# TSOC_PSoC4L.net
KiCad netlist of a schematic drawn in EAGLE
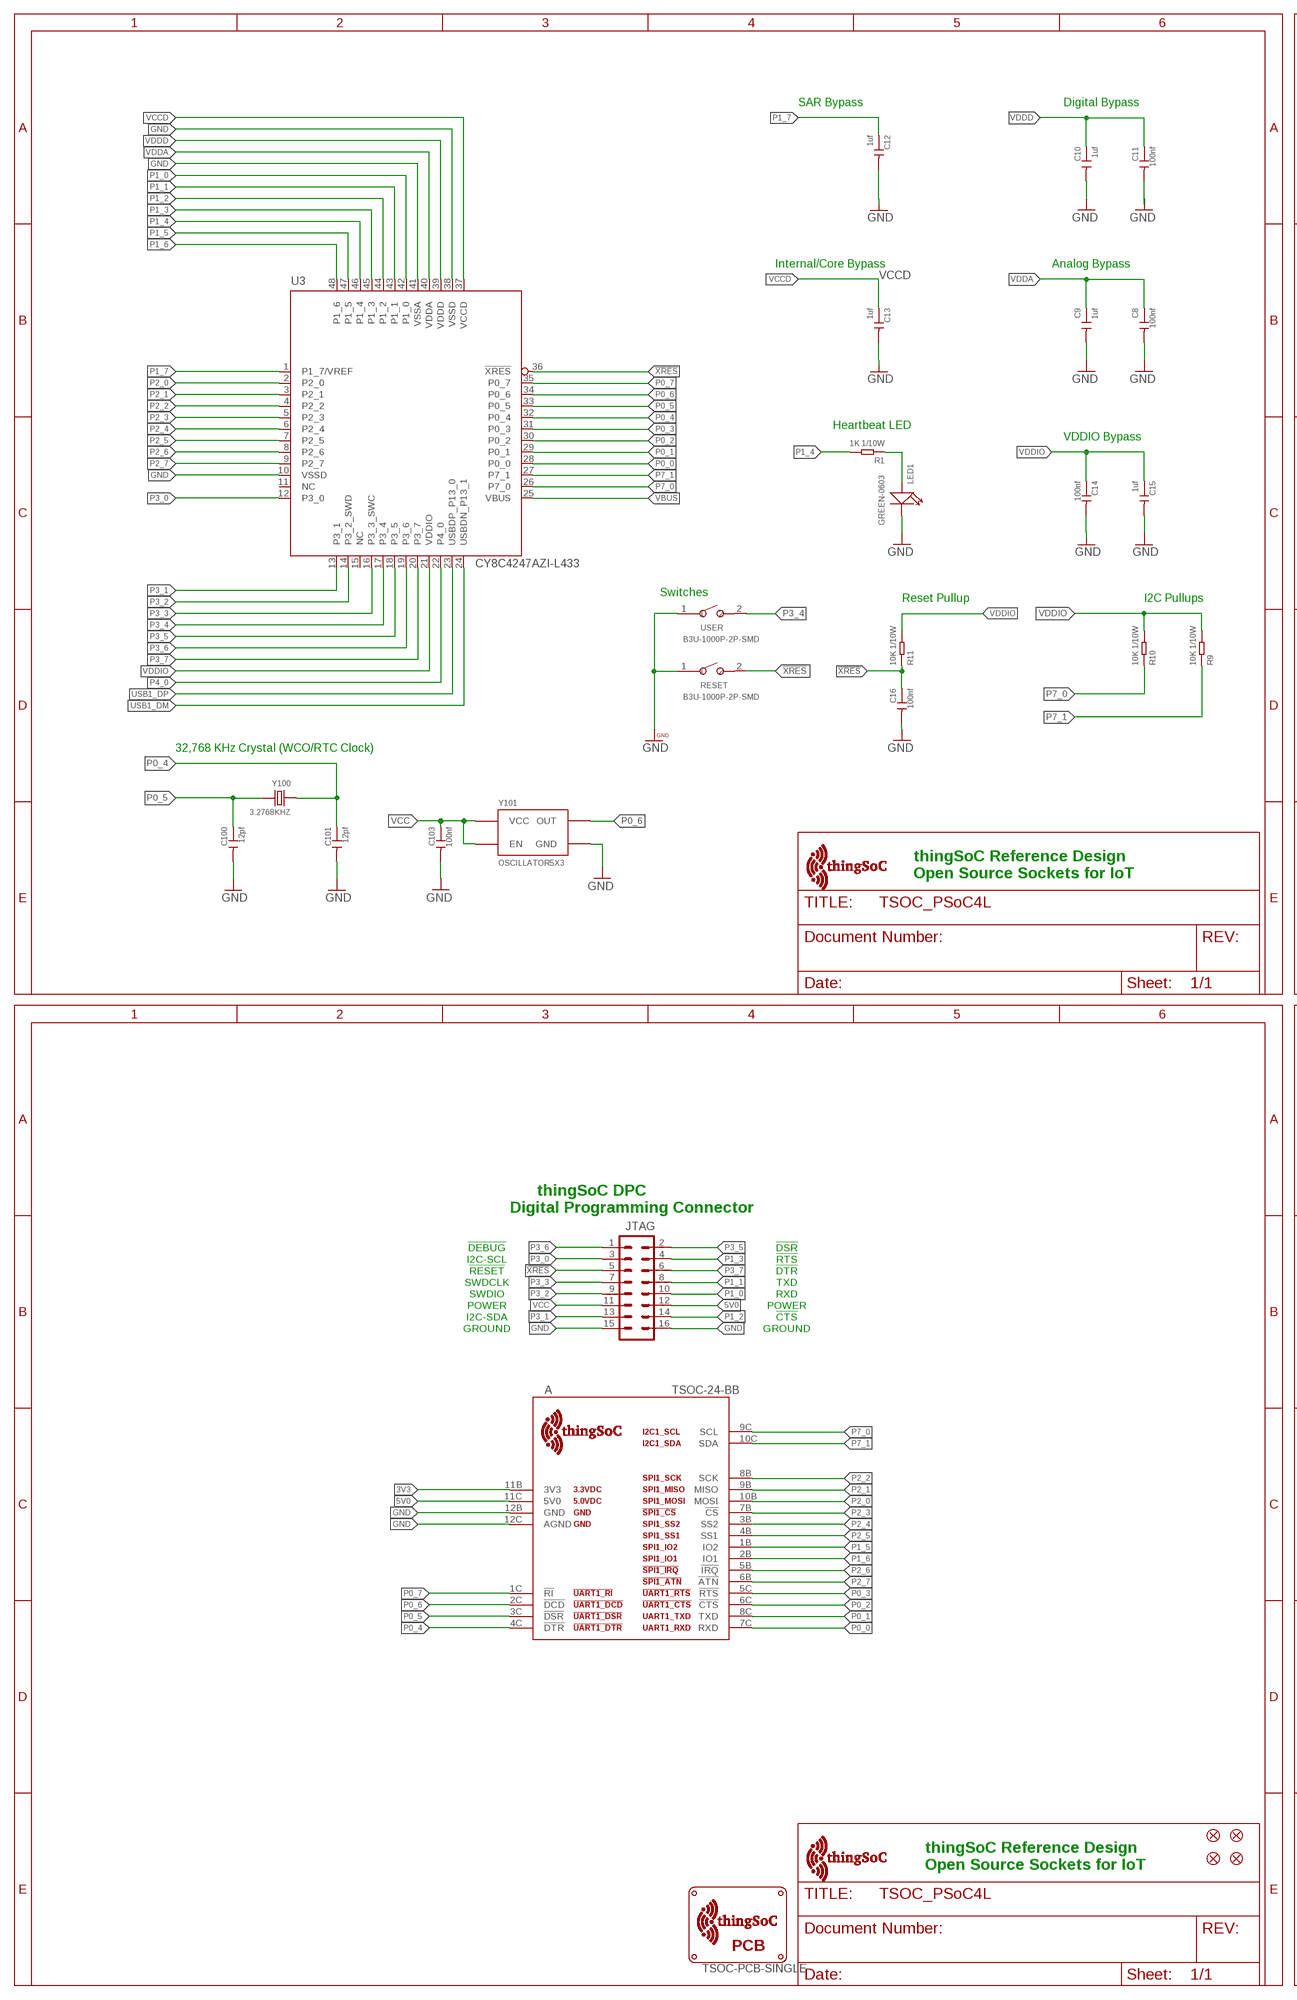
[diagram p0: schematic, sheet 1, part 1 of 2]
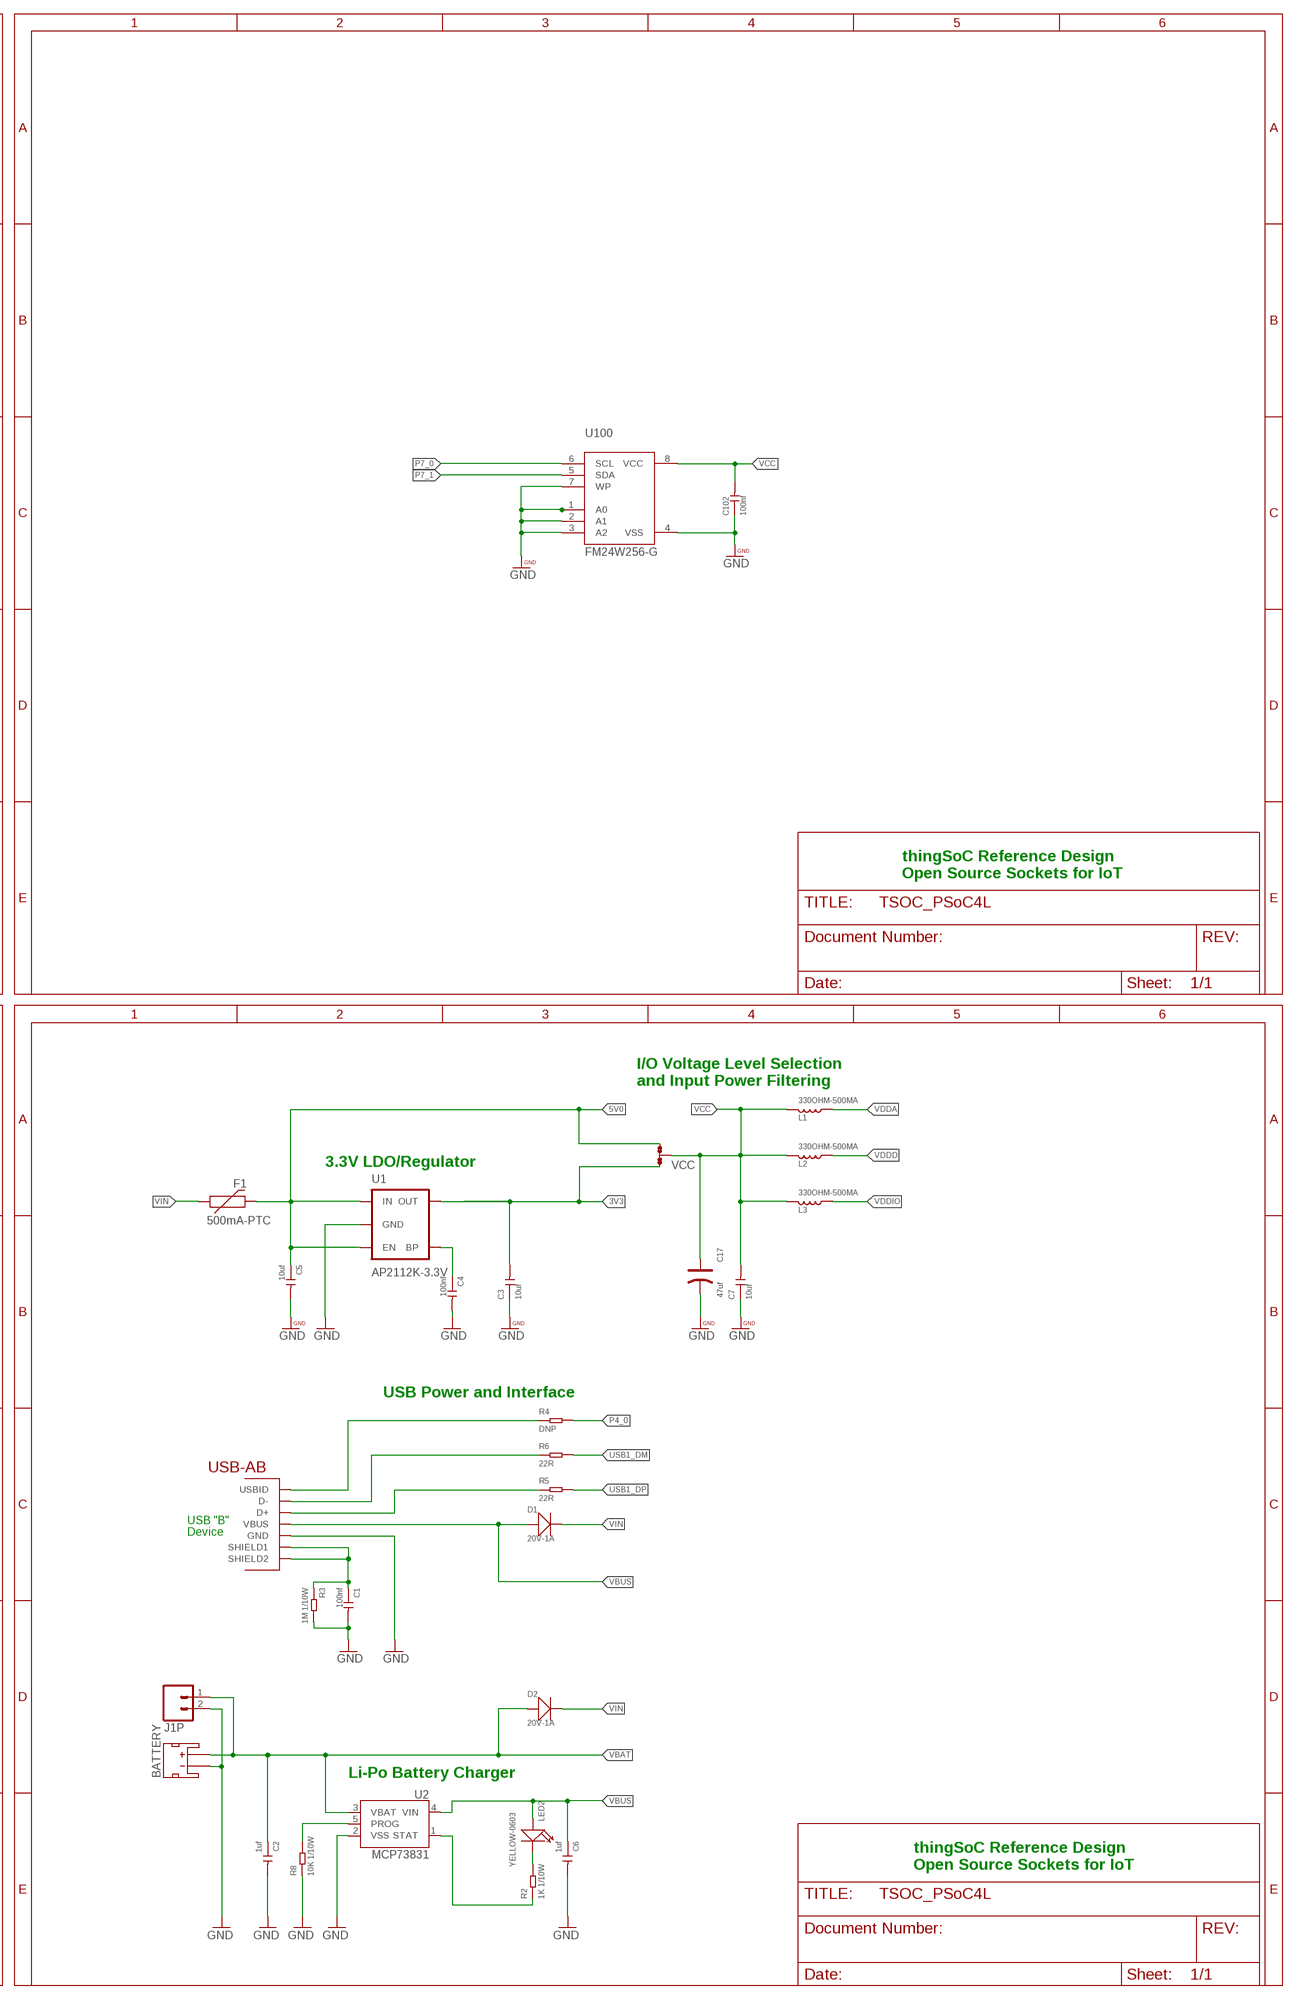
[diagram p1: schematic, sheet 1, part 2 of 2]

(export (version "E")
  (design (tool "Eeschema 10.0.6"))
  (components
    (comp (ref "A")
      (value "TSOC-24-BB")
      (footprint "eagle-import:TSOC-BB-S24")
      (libsource (lib "eagle-import") (part "TSOC-24-BB"))
    )
    (comp (ref "BATTERY")
      (value "JST_2MM_MALE")
      (footprint "eagle-import:JST-2-SMD")
      (libsource (lib "eagle-import") (part "JST_2MM_MALE"))
    )
    (comp (ref "C1")
      (value "100nf")
      (footprint "eagle-import:C0603")
      (fields (field (name "MPN") "CC0603KRX7R9BB104"))
      (libsource (lib "eagle-import") (part "CERAMIC-100NF-50V-10%-X7R(0603)"))
    )
    (comp (ref "C2")
      (value "1uf")
      (footprint "eagle-import:C0603")
      (fields (field (name "MPN") "CC0603KRX7R8BB105"))
      (libsource (lib "eagle-import") (part "CERAMIC-1UF-25V-10%-X7R(0603)"))
    )
    (comp (ref "C3")
      (value "10uf")
      (footprint "eagle-import:C0603")
      (fields (field (name "MPN") "CC0603KRX5R6BB106"))
      (libsource (lib "eagle-import") (part "CERAMIC-10UF-10V-10%-X5R(0603)"))
    )
    (comp (ref "C4")
      (value "100nf")
      (footprint "eagle-import:C0603")
      (fields (field (name "MPN") "CC0603KRX7R9BB104"))
      (libsource (lib "eagle-import") (part "CERAMIC-100NF-50V-10%-X7R(0603)"))
    )
    (comp (ref "C5")
      (value "10uf")
      (footprint "eagle-import:C0603")
      (fields (field (name "MPN") "CC0603KRX5R6BB106"))
      (libsource (lib "eagle-import") (part "CERAMIC-10UF-10V-10%-X5R(0603)"))
    )
    (comp (ref "C6")
      (value "1uf")
      (footprint "eagle-import:C0603")
      (fields (field (name "MPN") "CC0603KRX7R8BB105"))
      (libsource (lib "eagle-import") (part "CERAMIC-1UF-25V-10%-X7R(0603)"))
    )
    (comp (ref "C7")
      (value "10uf")
      (footprint "eagle-import:C0603")
      (fields (field (name "MPN") "CC0603KRX5R6BB106"))
      (libsource (lib "eagle-import") (part "CERAMIC-10UF-10V-10%-X5R(0603)"))
    )
    (comp (ref "C8")
      (value "100nf")
      (footprint "eagle-import:C0603")
      (fields (field (name "MPN") "CC0603KRX7R9BB104"))
      (libsource (lib "eagle-import") (part "CERAMIC-100NF-50V-10%-X7R(0603)"))
    )
    (comp (ref "C9")
      (value "1uf")
      (footprint "eagle-import:C0603")
      (fields (field (name "MPN") "CC0603KRX7R8BB105"))
      (libsource (lib "eagle-import") (part "CERAMIC-1UF-25V-10%-X7R(0603)"))
    )
    (comp (ref "C10")
      (value "1uf")
      (footprint "eagle-import:C0603")
      (fields (field (name "MPN") "CC0603KRX7R8BB105"))
      (libsource (lib "eagle-import") (part "CERAMIC-1UF-25V-10%-X7R(0603)"))
    )
    (comp (ref "C11")
      (value "100nf")
      (footprint "eagle-import:C0603")
      (fields (field (name "MPN") "CC0603KRX7R9BB104"))
      (libsource (lib "eagle-import") (part "CERAMIC-100NF-50V-10%-X7R(0603)"))
    )
    (comp (ref "C12")
      (value "1uf")
      (footprint "eagle-import:C0603")
      (fields (field (name "MPN") "CC0603KRX7R8BB105"))
      (libsource (lib "eagle-import") (part "CERAMIC-1UF-25V-10%-X7R(0603)"))
    )
    (comp (ref "C13")
      (value "1uf")
      (footprint "eagle-import:C0603")
      (fields (field (name "MPN") "CC0603KRX7R8BB105"))
      (libsource (lib "eagle-import") (part "CERAMIC-1UF-25V-10%-X7R(0603)"))
    )
    (comp (ref "C14")
      (value "100nf")
      (footprint "eagle-import:C0603")
      (fields (field (name "MPN") "CC0603KRX7R9BB104"))
      (libsource (lib "eagle-import") (part "CERAMIC-100NF-50V-10%-X7R(0603)"))
    )
    (comp (ref "C15")
      (value "1uf")
      (footprint "eagle-import:C0603")
      (fields (field (name "MPN") "CC0603KRX7R8BB105"))
      (libsource (lib "eagle-import") (part "CERAMIC-1UF-25V-10%-X7R(0603)"))
    )
    (comp (ref "C16")
      (value "100nf")
      (footprint "eagle-import:C0603")
      (fields (field (name "MPN") "CC0603KRX7R9BB104"))
      (libsource (lib "eagle-import") (part "CERAMIC-100NF-50V-10%-X7R(0603)"))
    )
    (comp (ref "C17")
      (value "47uf")
      (footprint "eagle-import:AVX-A")
      (fields (field (name "MPN") "TAJA476*006#NJ"))
      (libsource (lib "eagle-import") (part "TANTALUM-SMD-47UF-6.3V(AVX-A)"))
    )
    (comp (ref "C100")
      (value "12pf")
      (footprint "eagle-import:C0603")
      (fields (field (name "MPN") "CC0603JRNPO9BN120"))
      (libsource (lib "eagle-import") (part "CERAMIC-12PF-50V-5%-NPO(0603)"))
    )
    (comp (ref "C101")
      (value "12pf")
      (footprint "eagle-import:C0603")
      (fields (field (name "MPN") "CC0603JRNPO9BN120"))
      (libsource (lib "eagle-import") (part "CERAMIC-12PF-50V-5%-NPO(0603)"))
    )
    (comp (ref "C102")
      (value "100nf")
      (footprint "eagle-import:C0603")
      (fields (field (name "MPN") "CC0603KRX7R9BB104"))
      (libsource (lib "eagle-import") (part "CERAMIC-100NF-50V-10%-X7R(0603)"))
    )
    (comp (ref "C103")
      (value "100nf")
      (footprint "eagle-import:C0603")
      (fields (field (name "MPN") "CC0603KRX7R9BB104"))
      (libsource (lib "eagle-import") (part "CERAMIC-100NF-50V-10%-X7R(0603)"))
    )
    (comp (ref "D1")
      (value "20V-1A")
      (footprint "eagle-import:SOD-123")
      (fields (field (name "MPN") "B5819W"))
      (libsource (lib "eagle-import") (part "SMD-DIODE-SCHOTTKY-20V-1A(SOD-123)"))
    )
    (comp (ref "D2")
      (value "20V-1A")
      (footprint "eagle-import:SOD-123")
      (fields (field (name "MPN") "B5819W"))
      (libsource (lib "eagle-import") (part "SMD-DIODE-SCHOTTKY-20V-1A(SOD-123)"))
    )
    (comp (ref "F1")
      (value "500mA-PTC")
      (footprint "eagle-import:PTC-1206")
      (libsource (lib "eagle-import") (part "PTCSMD"))
    )
    (comp (ref "FID1")
      (value "FIDUCIALUFIDUCIAL")
      (footprint "eagle-import:MICRO-FIDUCIAL")
      (libsource (lib "eagle-import") (part "FIDUCIALUFIDUCIAL"))
    )
    (comp (ref "FID2")
      (value "FIDUCIALUFIDUCIAL")
      (footprint "eagle-import:MICRO-FIDUCIAL")
      (libsource (lib "eagle-import") (part "FIDUCIALUFIDUCIAL"))
    )
    (comp (ref "FID3")
      (value "FIDUCIALUFIDUCIAL")
      (footprint "eagle-import:MICRO-FIDUCIAL")
      (libsource (lib "eagle-import") (part "FIDUCIALUFIDUCIAL"))
    )
    (comp (ref "FID4")
      (value "FIDUCIALUFIDUCIAL")
      (footprint "eagle-import:MICRO-FIDUCIAL")
      (libsource (lib "eagle-import") (part "FIDUCIALUFIDUCIAL"))
    )
    (comp (ref "J1P")
      (value "M02-JST-2-PTH-NO_SILK")
      (footprint "eagle-import:JST-2-PTH-NS")
      (libsource (lib "eagle-import") (part "M02-JST-2-PTH-NO_SILK"))
    )
    (comp (ref "JTAG")
      (value "M08X2")
      (footprint "eagle-import:2X8")
      (libsource (lib "eagle-import") (part "M08X2"))
    )
    (comp (ref "L1")
      (value "330OHM-500MA")
      (footprint "eagle-import:L0603")
      (fields (field (name "MPN") "BLM18AG121SN1D"))
      (libsource (lib "eagle-import") (part "SMD-FERRITE-CHIP-120-OHM-500MA(0603)"))
    )
    (comp (ref "L2")
      (value "330OHM-500MA")
      (footprint "eagle-import:L0603")
      (fields (field (name "MPN") "BLM18AG121SN1D"))
      (libsource (lib "eagle-import") (part "SMD-FERRITE-CHIP-120-OHM-500MA(0603)"))
    )
    (comp (ref "L3")
      (value "330OHM-500MA")
      (footprint "eagle-import:L0603")
      (fields (field (name "MPN") "BLM18AG121SN1D"))
      (libsource (lib "eagle-import") (part "SMD-FERRITE-CHIP-120-OHM-500MA(0603)"))
    )
    (comp (ref "LED1")
      (value "GREEN-0603")
      (footprint "eagle-import:LED-0603")
      (fields (field (name "MPN") "19-217-G7C-AN1P2-3T"))
      (libsource (lib "eagle-import") (part "SMD-LED-CLEAR-GREEN(0603)"))
    )
    (comp (ref "LED2")
      (value "YELLOW-0603")
      (footprint "eagle-import:LED-0603")
      (fields (field (name "MPN") "19-217-Y5C-AM1N1VY-3T"))
      (libsource (lib "eagle-import") (part "SMD-LED-CLEAR-YELLOW(0603)"))
    )
    (comp (ref "R1")
      (value "1K 1/10W")
      (footprint "eagle-import:R0603")
      (fields (field (name "MPN") "RC0603JR-071KL"))
      (libsource (lib "eagle-import") (part "SMD-RES-1K-5%-1/10W(0603)"))
    )
    (comp (ref "R2")
      (value "1K 1/10W")
      (footprint "eagle-import:R0603")
      (fields (field (name "MPN") "RC0603JR-071KL"))
      (libsource (lib "eagle-import") (part "SMD-RES-1K-5%-1/10W(0603)"))
    )
    (comp (ref "R3")
      (value "1M 1/10W")
      (footprint "eagle-import:R0603")
      (fields (field (name "MPN") "RC0603JR-071ML"))
      (libsource (lib "eagle-import") (part "SMD-RES-1M-5%-1/10W(0603)"))
    )
    (comp (ref "R4")
      (value "DNP")
      (footprint "eagle-import:R0603")
      (fields (field (name "MPN") "RC0603JR-0722RL"))
      (libsource (lib "eagle-import") (part "SMD-RES-22R-5%-1/10W(0603)"))
    )
    (comp (ref "R5")
      (value "22R")
      (footprint "eagle-import:R0603")
      (fields (field (name "MPN") "RC0603JR-0722RL"))
      (libsource (lib "eagle-import") (part "SMD-RES-22R-5%-1/10W(0603)"))
    )
    (comp (ref "R6")
      (value "22R")
      (footprint "eagle-import:R0603")
      (fields (field (name "MPN") "RC0603JR-0722RL"))
      (libsource (lib "eagle-import") (part "SMD-RES-22R-5%-1/10W(0603)"))
    )
    (comp (ref "R8")
      (value "10K 1/10W")
      (footprint "eagle-import:R0603")
      (fields (field (name "MPN") "RC0603JR-0710KL"))
      (libsource (lib "eagle-import") (part "SMD-RES-10K-5%-1/10W(0603)"))
    )
    (comp (ref "R9")
      (value "10K 1/10W")
      (footprint "eagle-import:R0603")
      (fields (field (name "MPN") "RC0603JR-0710KL"))
      (libsource (lib "eagle-import") (part "SMD-RES-10K-5%-1/10W(0603)"))
    )
    (comp (ref "R10")
      (value "10K 1/10W")
      (footprint "eagle-import:R0603")
      (fields (field (name "MPN") "RC0603JR-0710KL"))
      (libsource (lib "eagle-import") (part "SMD-RES-10K-5%-1/10W(0603)"))
    )
    (comp (ref "R11")
      (value "10K 1/10W")
      (footprint "eagle-import:R0603")
      (fields (field (name "MPN") "RC0603JR-0710KL"))
      (libsource (lib "eagle-import") (part "SMD-RES-10K-5%-1/10W(0603)"))
    )
    (comp (ref "RESET")
      (value "B3U-1000P-2P-SMD")
      (footprint "eagle-import:SW2-2.6-3.0X2.5X1.2+0.4MM")
      (libsource (lib "eagle-import") (part "SMD-BUTTON(2P-3.0X2.5X1.2+0.4MM)-B3U-1000P-2P-SMD"))
    )
    (comp (ref "U$1")
      (value "TSOC-PCB-SINGLE")
      (footprint "eagle-import:TSOC-BB-BRD-DIM")
      (libsource (lib "eagle-import") (part "TSOC-PCB-SINGLE"))
    )
    (comp (ref "U$100")
      (value "TSOC-LOGO-LRG")
      (footprint "eagle-import:TSOC-LOGO-LRG")
      (libsource (lib "eagle-import") (part "TSOC-LOGO-LRG"))
    )
    (comp (ref "U$101")
      (value "TSOC-LOGO-SMALL")
      (footprint "eagle-import:TSOC-LOGO-SML")
      (libsource (lib "eagle-import") (part "TSOC-LOGO-SMALL"))
    )
    (comp (ref "U1")
      (value "AP2112K-3.3V")
      (footprint "eagle-import:SOT23-5")
      (libsource (lib "eagle-import") (part "V_REG_LDOSMD"))
    )
    (comp (ref "U2")
      (value "MCP73831")
      (footprint "eagle-import:SOT23-5")
      (libsource (lib "eagle-import") (part "MCP73831"))
    )
    (comp (ref "U3")
      (value "CY8C4247AZI-L433")
      (footprint "eagle-import:TQFP-7X7-48")
      (libsource (lib "eagle-import") (part "CY8C4247AZI-L433"))
    )
    (comp (ref "U100")
      (value "FM24W256-G")
      (footprint "eagle-import:SO08")
      (libsource (lib "eagle-import") (part "FM24W256-G"))
    )
    (comp (ref "USB")
      (value "USB_AB")
      (footprint "eagle-import:USB-AB-MICRO-SMD")
      (libsource (lib "eagle-import") (part "USB_AB"))
    )
    (comp (ref "USER")
      (value "B3U-1000P-2P-SMD")
      (footprint "eagle-import:SW2-2.6-3.0X2.5X1.2+0.4MM")
      (libsource (lib "eagle-import") (part "SMD-BUTTON(2P-3.0X2.5X1.2+0.4MM)-B3U-1000P-2P-SMD"))
    )
    (comp (ref "VCC")
      (value "JMP-3-1_2")
      (footprint "eagle-import:JMP-3-1_2")
      (libsource (lib "eagle-import") (part "JMP-3-1_2"))
    )
    (comp (ref "Y100")
      (value "3.2768KHZ")
      (footprint "eagle-import:X2-SMD-L2.0X1.2X0.55MM")
      (fields (field (name "MPN") "FC-12M"))
      (libsource (lib "eagle-import") (part "SMD-CRYSTAL-32.768KHZ-12.5PF-20PPM-90K(2P-L2.0X1.2MM)"))
    )
    (comp (ref "Y101")
      (value "OSCILLATOR5X3")
      (footprint "eagle-import:CRYSTAL-SMD-5X3")
      (libsource (lib "eagle-import") (part "OSCILLATOR5X3"))
    )
  )
  (nets
    (net (code "1") (name "/~{XRES}") (class "Default")
      (node (ref "C16") (pin "1") (pinfunction "1_1") (pintype "passive"))
      (node (ref "JTAG") (pin "5") (pinfunction "5_5") (pintype "passive"))
      (node (ref "R11") (pin "1") (pinfunction "1_1") (pintype "passive"))
      (node (ref "RESET") (pin "2") (pinfunction "2_2") (pintype "bidirectional"))
      (node (ref "U3") (pin "36") (pinfunction "~{XRES}_36") (pintype "bidirectional"))
    )
    (net (code "2") (name "3V3") (class "Default")
      (node (ref "A") (pin "11B") (pinfunction "3V3_11B") (pintype "bidirectional"))
      (node (ref "C3") (pin "2") (pinfunction "2_2") (pintype "passive"))
      (node (ref "U1") (pin "5") (pinfunction "OUT_5") (pintype "passive"))
      (node (ref "VCC") (pin "1") (pinfunction "1_1") (pintype "passive"))
    )
    (net (code "3") (name "5V0") (class "Default")
      (node (ref "A") (pin "11C") (pinfunction "5V0_11C") (pintype "bidirectional"))
      (node (ref "C5") (pin "1") (pinfunction "1_1") (pintype "passive"))
      (node (ref "F1") (pin "2") (pinfunction "2_2") (pintype "bidirectional"))
      (node (ref "JTAG") (pin "12") (pinfunction "12_12") (pintype "passive"))
      (node (ref "U1") (pin "1") (pinfunction "IN_1") (pintype "input"))
      (node (ref "U1") (pin "3") (pinfunction "EN_3") (pintype "input"))
      (node (ref "VCC") (pin "3") (pinfunction "3_3") (pintype "passive"))
    )
    (net (code "4") (name "GND") (class "Default")
      (node (ref "A") (pin "12B") (pinfunction "GND_12B") (pintype "bidirectional"))
      (node (ref "A") (pin "12C") (pinfunction "AGND_12C") (pintype "bidirectional"))
      (node (ref "BATTERY") (pin "1") (pinfunction "-_1") (pintype "bidirectional"))
      (node (ref "C1") (pin "2") (pinfunction "2_2") (pintype "passive"))
      (node (ref "C10") (pin "2") (pinfunction "2_2") (pintype "passive"))
      (node (ref "C100") (pin "2") (pinfunction "2_2") (pintype "passive"))
      (node (ref "C101") (pin "2") (pinfunction "2_2") (pintype "passive"))
      (node (ref "C102") (pin "1") (pinfunction "1_1") (pintype "passive"))
      (node (ref "C103") (pin "2") (pinfunction "2_2") (pintype "passive"))
      (node (ref "C11") (pin "2") (pinfunction "2_2") (pintype "passive"))
      (node (ref "C12") (pin "2") (pinfunction "2_2") (pintype "passive"))
      (node (ref "C13") (pin "2") (pinfunction "2_2") (pintype "passive"))
      (node (ref "C14") (pin "2") (pinfunction "2_2") (pintype "passive"))
      (node (ref "C15") (pin "2") (pinfunction "2_2") (pintype "passive"))
      (node (ref "C16") (pin "2") (pinfunction "2_2") (pintype "passive"))
      (node (ref "C17") (pin "-") (pinfunction "-_-") (pintype "passive"))
      (node (ref "C2") (pin "2") (pinfunction "2_2") (pintype "passive"))
      (node (ref "C3") (pin "1") (pinfunction "1_1") (pintype "passive"))
      (node (ref "C4") (pin "2") (pinfunction "2_2") (pintype "passive"))
      (node (ref "C5") (pin "2") (pinfunction "2_2") (pintype "passive"))
      (node (ref "C6") (pin "2") (pinfunction "2_2") (pintype "passive"))
      (node (ref "C7") (pin "1") (pinfunction "1_1") (pintype "passive"))
      (node (ref "C8") (pin "2") (pinfunction "2_2") (pintype "passive"))
      (node (ref "C9") (pin "2") (pinfunction "2_2") (pintype "passive"))
      (node (ref "J1P") (pin "2") (pinfunction "2_2") (pintype "passive"))
      (node (ref "JTAG") (pin "15") (pinfunction "15_15") (pintype "passive"))
      (node (ref "JTAG") (pin "16") (pinfunction "16_16") (pintype "passive"))
      (node (ref "LED1") (pin "-") (pinfunction "-_-") (pintype "passive"))
      (node (ref "R3") (pin "2") (pinfunction "2_2") (pintype "passive"))
      (node (ref "R8") (pin "1") (pinfunction "1_1") (pintype "passive"))
      (node (ref "RESET") (pin "1") (pinfunction "1_1") (pintype "bidirectional"))
      (node (ref "U1") (pin "2") (pinfunction "GND_2") (pintype "input"))
      (node (ref "U100") (pin "1") (pinfunction "A0_1") (pintype "bidirectional"))
      (node (ref "U100") (pin "2") (pinfunction "A1_2") (pintype "bidirectional"))
      (node (ref "U100") (pin "3") (pinfunction "A2_3") (pintype "bidirectional"))
      (node (ref "U100") (pin "4") (pinfunction "VSS_4") (pintype "power_in"))
      (node (ref "U100") (pin "7") (pinfunction "WP_7") (pintype "bidirectional"))
      (node (ref "U2") (pin "2") (pinfunction "VSS_2") (pintype "power_in"))
      (node (ref "U3") (pin "10") (pinfunction "VSSD_10") (pintype "bidirectional"))
      (node (ref "U3") (pin "38") (pinfunction "VSSD_38") (pintype "bidirectional"))
      (node (ref "U3") (pin "41") (pinfunction "VSSA_41") (pintype "bidirectional"))
      (node (ref "USB") (pin "GND") (pinfunction "GND_GND") (pintype "bidirectional"))
      (node (ref "USER") (pin "1") (pinfunction "1_1") (pintype "bidirectional"))
      (node (ref "Y101") (pin "2") (pinfunction "GND_2") (pintype "bidirectional"))
    )
    (net (code "5") (name "Net-(C1-Pad1)") (class "Default")
      (node (ref "C1") (pin "1") (pinfunction "1_1") (pintype "passive"))
      (node (ref "R3") (pin "1") (pinfunction "1_1") (pintype "passive"))
      (node (ref "USB") (pin "SHIELD1") (pinfunction "SHIELD1_SHIELD1") (pintype "bidirectional"))
      (node (ref "USB") (pin "SHIELD2") (pinfunction "SHIELD2_SHIELD2") (pintype "bidirectional"))
    )
    (net (code "6") (name "Net-(LED1-Pad+)") (class "Default")
      (node (ref "LED1") (pin "+") (pinfunction "+_+") (pintype "passive"))
      (node (ref "R1") (pin "1") (pinfunction "1_1") (pintype "passive"))
    )
    (net (code "7") (name "Net-(LED2-Pad-)") (class "Default")
      (node (ref "LED2") (pin "-") (pinfunction "-_-") (pintype "passive"))
      (node (ref "R2") (pin "2") (pinfunction "2_2") (pintype "passive"))
    )
    (net (code "8") (name "Net-(R5-Pad1)") (class "Default")
      (node (ref "R5") (pin "1") (pinfunction "1_1") (pintype "passive"))
      (node (ref "USB") (pin "D+") (pinfunction "D+_D+") (pintype "bidirectional"))
    )
    (net (code "9") (name "Net-(R6-Pad1)") (class "Default")
      (node (ref "R6") (pin "1") (pinfunction "1_1") (pintype "passive"))
      (node (ref "USB") (pin "D-") (pinfunction "D-_D-") (pintype "bidirectional"))
    )
    (net (code "10") (name "Net-(U1-BP)") (class "Default")
      (node (ref "C4") (pin "1") (pinfunction "1_1") (pintype "passive"))
      (node (ref "U1") (pin "4") (pinfunction "BP_4") (pintype "input"))
    )
    (net (code "11") (name "Net-(U2-PROG)") (class "Default")
      (node (ref "R8") (pin "2") (pinfunction "2_2") (pintype "passive"))
      (node (ref "U2") (pin "5") (pinfunction "PROG_5") (pintype "input"))
    )
    (net (code "12") (name "Net-(U2-STAT)") (class "Default")
      (node (ref "R2") (pin "1") (pinfunction "1_1") (pintype "passive"))
      (node (ref "U2") (pin "1") (pinfunction "STAT_1") (pintype "output"))
    )
    (net (code "13") (name "Net-(USB-USBID)") (class "Default")
      (node (ref "R4") (pin "1") (pinfunction "1_1") (pintype "passive"))
      (node (ref "USB") (pin "ID") (pinfunction "USBID_ID") (pintype "bidirectional"))
    )
    (net (code "14") (name "P0_0") (class "Default")
      (node (ref "A") (pin "7C") (pinfunction "RXD_7C") (pintype "bidirectional"))
      (node (ref "U3") (pin "28") (pinfunction "P0_0_28") (pintype "bidirectional"))
    )
    (net (code "15") (name "P0_1") (class "Default")
      (node (ref "A") (pin "8C") (pinfunction "TXD_8C") (pintype "bidirectional"))
      (node (ref "U3") (pin "29") (pinfunction "P0_1_29") (pintype "bidirectional"))
    )
    (net (code "16") (name "P0_2") (class "Default")
      (node (ref "A") (pin "6C") (pinfunction "~{CTS}_6C") (pintype "bidirectional"))
      (node (ref "U3") (pin "30") (pinfunction "P0_2_30") (pintype "input"))
    )
    (net (code "17") (name "P0_3") (class "Default")
      (node (ref "A") (pin "5C") (pinfunction "~{RTS}_5C") (pintype "bidirectional"))
      (node (ref "U3") (pin "31") (pinfunction "P0_3_31") (pintype "bidirectional"))
    )
    (net (code "18") (name "P0_4") (class "Default")
      (node (ref "A") (pin "4C") (pinfunction "~{DTR}_4C") (pintype "bidirectional"))
      (node (ref "C101") (pin "1") (pinfunction "1_1") (pintype "passive"))
      (node (ref "U3") (pin "32") (pinfunction "P0_4_32") (pintype "bidirectional"))
      (node (ref "Y100") (pin "1") (pinfunction "1_1") (pintype "passive"))
    )
    (net (code "19") (name "P0_5") (class "Default")
      (node (ref "A") (pin "3C") (pinfunction "~{DSR}_3C") (pintype "bidirectional"))
      (node (ref "C100") (pin "1") (pinfunction "1_1") (pintype "passive"))
      (node (ref "U3") (pin "33") (pinfunction "P0_5_33") (pintype "bidirectional"))
      (node (ref "Y100") (pin "2") (pinfunction "2_2") (pintype "passive"))
    )
    (net (code "20") (name "P0_6") (class "Default")
      (node (ref "A") (pin "2C") (pinfunction "~{DCD}_2C") (pintype "bidirectional"))
      (node (ref "U3") (pin "34") (pinfunction "P0_6_34") (pintype "power_in"))
      (node (ref "Y101") (pin "3") (pinfunction "OUT_3") (pintype "bidirectional"))
    )
    (net (code "21") (name "P0_7") (class "Default")
      (node (ref "A") (pin "1C") (pinfunction "~{RI}_1C") (pintype "bidirectional"))
      (node (ref "U3") (pin "35") (pinfunction "P0_7_35") (pintype "bidirectional"))
    )
    (net (code "22") (name "P1_0") (class "Default")
      (node (ref "JTAG") (pin "10") (pinfunction "10_10") (pintype "passive"))
      (node (ref "U3") (pin "42") (pinfunction "P1_0_42") (pintype "bidirectional"))
    )
    (net (code "23") (name "P1_1") (class "Default")
      (node (ref "JTAG") (pin "8") (pinfunction "8_8") (pintype "passive"))
      (node (ref "U3") (pin "43") (pinfunction "P1_1_43") (pintype "bidirectional"))
    )
    (net (code "24") (name "P1_2") (class "Default")
      (node (ref "JTAG") (pin "14") (pinfunction "14_14") (pintype "passive"))
      (node (ref "U3") (pin "44") (pinfunction "P1_2_44") (pintype "power_in"))
    )
    (net (code "25") (name "P1_3") (class "Default")
      (node (ref "JTAG") (pin "4") (pinfunction "4_4") (pintype "passive"))
      (node (ref "U3") (pin "45") (pinfunction "P1_3_45") (pintype "bidirectional"))
    )
    (net (code "26") (name "P1_4") (class "Default")
      (node (ref "R1") (pin "2") (pinfunction "2_2") (pintype "passive"))
      (node (ref "U3") (pin "46") (pinfunction "P1_4_46") (pintype "bidirectional"))
    )
    (net (code "27") (name "P1_5") (class "Default")
      (node (ref "A") (pin "1B") (pinfunction "IO2_1B") (pintype "bidirectional"))
      (node (ref "U3") (pin "47") (pinfunction "P1_5_47") (pintype "bidirectional"))
    )
    (net (code "28") (name "P1_6") (class "Default")
      (node (ref "A") (pin "2B") (pinfunction "IO1_2B") (pintype "bidirectional"))
      (node (ref "U3") (pin "48") (pinfunction "P1_6_48") (pintype "bidirectional"))
    )
    (net (code "29") (name "P1_7") (class "Default")
      (node (ref "C12") (pin "1") (pinfunction "1_1") (pintype "passive"))
      (node (ref "U3") (pin "1") (pinfunction "P1_7/VREF_1") (pintype "bidirectional"))
    )
    (net (code "30") (name "P2_0") (class "Default")
      (node (ref "A") (pin "10B") (pinfunction "MOSI_10B") (pintype "bidirectional"))
      (node (ref "U3") (pin "2") (pinfunction "P2_0_2") (pintype "bidirectional"))
    )
    (net (code "31") (name "P2_1") (class "Default")
      (node (ref "A") (pin "9B") (pinfunction "MISO_9B") (pintype "bidirectional"))
      (node (ref "U3") (pin "3") (pinfunction "P2_1_3") (pintype "bidirectional"))
    )
    (net (code "32") (name "P2_2") (class "Default")
      (node (ref "A") (pin "8B") (pinfunction "SCK_8B") (pintype "bidirectional"))
      (node (ref "U3") (pin "4") (pinfunction "P2_2_4") (pintype "power_in"))
    )
    (net (code "33") (name "P2_3") (class "Default")
      (node (ref "A") (pin "7B") (pinfunction "~{CS}_7B") (pintype "bidirectional"))
      (node (ref "U3") (pin "5") (pinfunction "P2_3_5") (pintype "bidirectional"))
    )
    (net (code "34") (name "P2_4") (class "Default")
      (node (ref "A") (pin "3B") (pinfunction "SS2_3B") (pintype "bidirectional"))
      (node (ref "U3") (pin "6") (pinfunction "P2_4_6") (pintype "bidirectional"))
    )
    (net (code "35") (name "P2_5") (class "Default")
      (node (ref "A") (pin "4B") (pinfunction "SS1_4B") (pintype "bidirectional"))
      (node (ref "U3") (pin "7") (pinfunction "P2_5_7") (pintype "bidirectional"))
    )
    (net (code "36") (name "P2_6") (class "Default")
      (node (ref "A") (pin "5B") (pinfunction "~{IRQ}_5B") (pintype "bidirectional"))
      (node (ref "U3") (pin "8") (pinfunction "P2_6_8") (pintype "power_in"))
    )
    (net (code "37") (name "P2_7") (class "Default")
      (node (ref "A") (pin "6B") (pinfunction "~{ATN}_6B") (pintype "bidirectional"))
      (node (ref "U3") (pin "9") (pinfunction "P2_7_9") (pintype "bidirectional"))
    )
    (net (code "38") (name "P3_0") (class "Default")
      (node (ref "JTAG") (pin "3") (pinfunction "3_3") (pintype "passive"))
      (node (ref "U3") (pin "12") (pinfunction "P3_0_12") (pintype "bidirectional"))
    )
    (net (code "39") (name "P3_1") (class "Default")
      (node (ref "JTAG") (pin "13") (pinfunction "13_13") (pintype "passive"))
      (node (ref "U3") (pin "13") (pinfunction "P3_1_13") (pintype "bidirectional"))
    )
    (net (code "40") (name "P3_2") (class "Default")
      (node (ref "JTAG") (pin "9") (pinfunction "9_9") (pintype "passive"))
      (node (ref "U3") (pin "14") (pinfunction "P3_2_SWD_14") (pintype "bidirectional"))
    )
    (net (code "41") (name "P3_3") (class "Default")
      (node (ref "JTAG") (pin "7") (pinfunction "7_7") (pintype "passive"))
      (node (ref "U3") (pin "16") (pinfunction "P3_3_SWC_16") (pintype "bidirectional"))
    )
    (net (code "42") (name "P3_4") (class "Default")
      (node (ref "U3") (pin "17") (pinfunction "P3_4_17") (pintype "bidirectional"))
      (node (ref "USER") (pin "2") (pinfunction "2_2") (pintype "bidirectional"))
    )
    (net (code "43") (name "P3_5") (class "Default")
      (node (ref "JTAG") (pin "2") (pinfunction "2_2") (pintype "passive"))
      (node (ref "U3") (pin "18") (pinfunction "P3_5_18") (pintype "bidirectional"))
    )
    (net (code "44") (name "P3_6") (class "Default")
      (node (ref "JTAG") (pin "1") (pinfunction "1_1") (pintype "passive"))
      (node (ref "U3") (pin "19") (pinfunction "P3_6_19") (pintype "power_in"))
    )
    (net (code "45") (name "P3_7") (class "Default")
      (node (ref "JTAG") (pin "6") (pinfunction "6_6") (pintype "passive"))
      (node (ref "U3") (pin "20") (pinfunction "P3_7_20") (pintype "bidirectional"))
    )
    (net (code "46") (name "P4_0") (class "Default")
      (node (ref "R4") (pin "2") (pinfunction "2_2") (pintype "passive"))
      (node (ref "U3") (pin "22") (pinfunction "P4_0_22") (pintype "bidirectional"))
    )
    (net (code "47") (name "P7_0") (class "Default")
      (node (ref "A") (pin "9C") (pinfunction "SCL_9C") (pintype "bidirectional"))
      (node (ref "R10") (pin "1") (pinfunction "1_1") (pintype "passive"))
      (node (ref "U100") (pin "6") (pinfunction "SCL_6") (pintype "bidirectional"))
      (node (ref "U3") (pin "26") (pinfunction "P7_0_26") (pintype "bidirectional"))
    )
    (net (code "48") (name "P7_1") (class "Default")
      (node (ref "A") (pin "10C") (pinfunction "SDA_10C") (pintype "bidirectional"))
      (node (ref "R9") (pin "1") (pinfunction "1_1") (pintype "passive"))
      (node (ref "U100") (pin "5") (pinfunction "SDA_5") (pintype "bidirectional"))
      (node (ref "U3") (pin "27") (pinfunction "P7_1_27") (pintype "bidirectional"))
    )
    (net (code "49") (name "USB1_DM") (class "Default")
      (node (ref "R6") (pin "2") (pinfunction "2_2") (pintype "passive"))
      (node (ref "U3") (pin "24") (pinfunction "USBDN_P13_1_24") (pintype "bidirectional"))
    )
    (net (code "50") (name "USB1_DP") (class "Default")
      (node (ref "R5") (pin "2") (pinfunction "2_2") (pintype "passive"))
      (node (ref "U3") (pin "23") (pinfunction "USBDP_P13_0_23") (pintype "bidirectional"))
    )
    (net (code "51") (name "VBAT") (class "Default")
      (node (ref "BATTERY") (pin "2") (pinfunction "+_2") (pintype "bidirectional"))
      (node (ref "C2") (pin "1") (pinfunction "1_1") (pintype "passive"))
      (node (ref "D2") (pin "+") (pinfunction "+_+") (pintype "passive"))
      (node (ref "J1P") (pin "1") (pinfunction "1_1") (pintype "passive"))
      (node (ref "U2") (pin "3") (pinfunction "VBAT_3") (pintype "power_in"))
    )
    (net (code "52") (name "VBUS") (class "Default")
      (node (ref "C6") (pin "1") (pinfunction "1_1") (pintype "passive"))
      (node (ref "D1") (pin "+") (pinfunction "+_+") (pintype "passive"))
      (node (ref "LED2") (pin "+") (pinfunction "+_+") (pintype "passive"))
      (node (ref "U2") (pin "4") (pinfunction "VIN_4") (pintype "power_in"))
      (node (ref "U3") (pin "25") (pinfunction "VBUS_25") (pintype "bidirectional"))
      (node (ref "USB") (pin "VBUS") (pinfunction "VBUS_VBUS") (pintype "bidirectional"))
    )
    (net (code "53") (name "VCC") (class "Default")
      (node (ref "C102") (pin "2") (pinfunction "2_2") (pintype "passive"))
      (node (ref "C103") (pin "1") (pinfunction "1_1") (pintype "passive"))
      (node (ref "C17") (pin "+") (pinfunction "+_+") (pintype "passive"))
      (node (ref "C7") (pin "2") (pinfunction "2_2") (pintype "passive"))
      (node (ref "JTAG") (pin "11") (pinfunction "11_11") (pintype "passive"))
      (node (ref "L1") (pin "1") (pinfunction "1_1") (pintype "passive"))
      (node (ref "L2") (pin "1") (pinfunction "1_1") (pintype "passive"))
      (node (ref "L3") (pin "1") (pinfunction "1_1") (pintype "passive"))
      (node (ref "U100") (pin "8") (pinfunction "VCC_8") (pintype "power_in"))
      (node (ref "VCC") (pin "2") (pinfunction "2_2") (pintype "passive"))
      (node (ref "Y101") (pin "1") (pinfunction "EN_1") (pintype "bidirectional"))
      (node (ref "Y101") (pin "4") (pinfunction "VCC_4") (pintype "bidirectional"))
    )
    (net (code "54") (name "VCCD") (class "Default")
      (node (ref "C13") (pin "1") (pinfunction "1_1") (pintype "passive"))
      (node (ref "U3") (pin "37") (pinfunction "VCCD_37") (pintype "bidirectional"))
    )
    (net (code "55") (name "VDDA") (class "Default")
      (node (ref "C8") (pin "1") (pinfunction "1_1") (pintype "passive"))
      (node (ref "C9") (pin "1") (pinfunction "1_1") (pintype "passive"))
      (node (ref "L1") (pin "2") (pinfunction "2_2") (pintype "passive"))
      (node (ref "U3") (pin "40") (pinfunction "VDDA_40") (pintype "bidirectional"))
    )
    (net (code "56") (name "VDDD") (class "Default")
      (node (ref "C10") (pin "1") (pinfunction "1_1") (pintype "passive"))
      (node (ref "C11") (pin "1") (pinfunction "1_1") (pintype "passive"))
      (node (ref "L2") (pin "2") (pinfunction "2_2") (pintype "passive"))
      (node (ref "U3") (pin "39") (pinfunction "VDDD_39") (pintype "bidirectional"))
    )
    (net (code "57") (name "VDDIO") (class "Default")
      (node (ref "C14") (pin "1") (pinfunction "1_1") (pintype "passive"))
      (node (ref "C15") (pin "1") (pinfunction "1_1") (pintype "passive"))
      (node (ref "L3") (pin "2") (pinfunction "2_2") (pintype "passive"))
      (node (ref "R10") (pin "2") (pinfunction "2_2") (pintype "passive"))
      (node (ref "R11") (pin "2") (pinfunction "2_2") (pintype "passive"))
      (node (ref "R9") (pin "2") (pinfunction "2_2") (pintype "passive"))
      (node (ref "U3") (pin "21") (pinfunction "VDDIO_21") (pintype "bidirectional"))
    )
    (net (code "58") (name "VIN") (class "Default")
      (node (ref "D1") (pin "-") (pinfunction "-_-") (pintype "passive"))
      (node (ref "D2") (pin "-") (pinfunction "-_-") (pintype "passive"))
      (node (ref "F1") (pin "1") (pinfunction "1_1") (pintype "bidirectional"))
    )
    (net (code "59") (name "unconnected-(BATTERY-PAD1-PadNC1)") (class "Default")
      (node (ref "BATTERY") (pin "NC1") (pinfunction "PAD1_NC1") (pintype "bidirectional"))
    )
    (net (code "60") (name "unconnected-(BATTERY-PAD2-PadNC2)") (class "Default")
      (node (ref "BATTERY") (pin "NC2") (pinfunction "PAD2_NC2") (pintype "bidirectional"))
    )
    (net (code "61") (name "unconnected-(U3-NC-Pad11)") (class "Default")
      (node (ref "U3") (pin "11") (pinfunction "NC_11") (pintype "bidirectional"))
    )
    (net (code "62") (name "unconnected-(U3-NC-Pad15)") (class "Default")
      (node (ref "U3") (pin "15") (pinfunction "NC_15") (pintype "bidirectional"))
    )
  )
)
